# 02_FPGA_CORE.net
KiCad netlist of a schematic drawn in Altium Designer
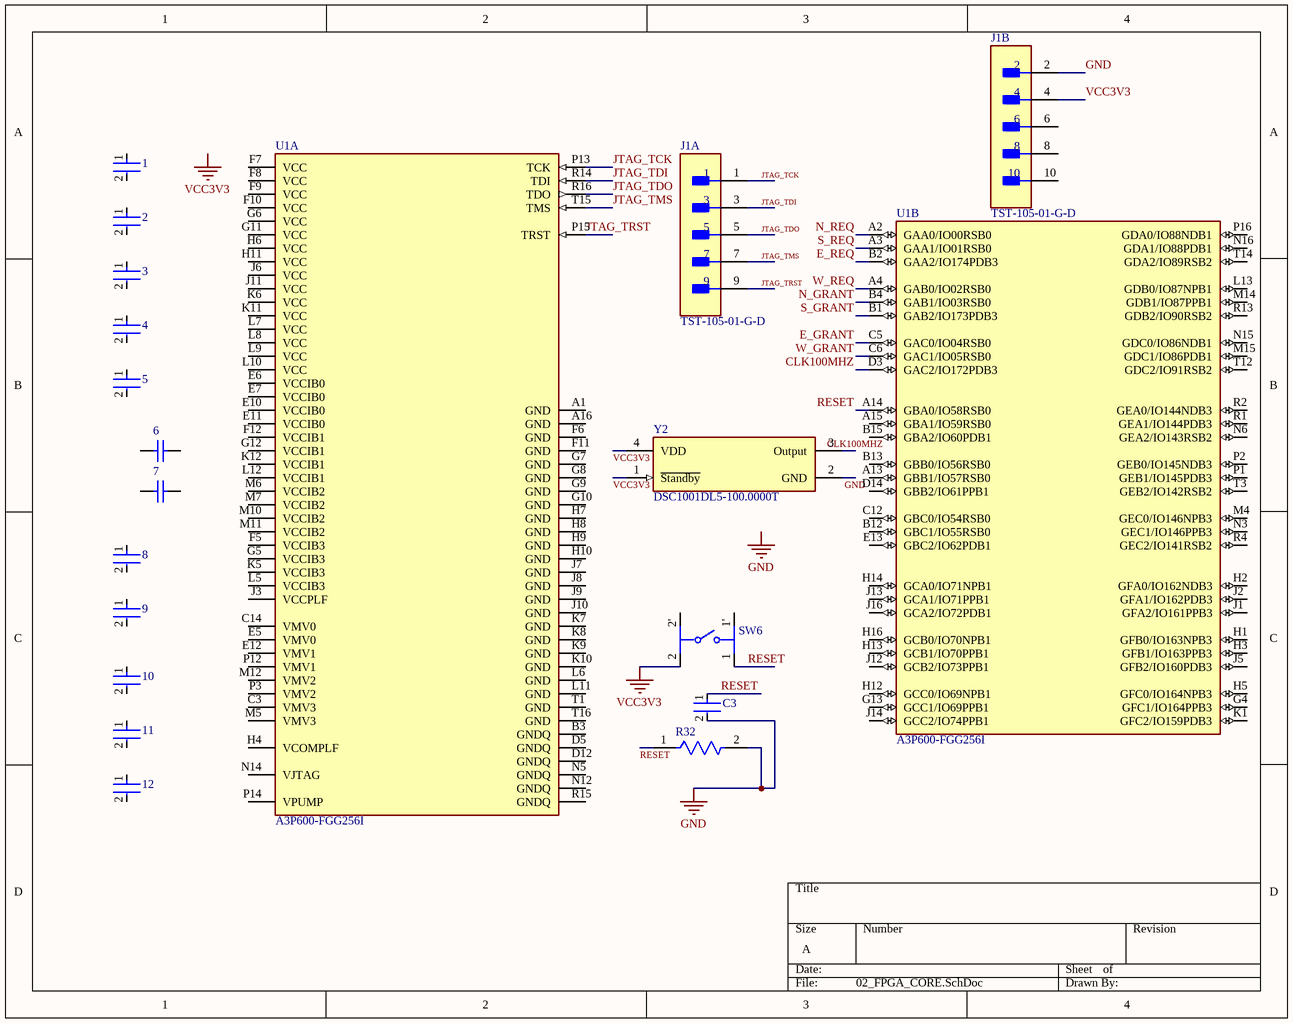
[diagram p0: 02_FPGA_CORE.SchDoc]

(export (version "E")
  (design (tool "Eeschema 10.0.6"))
  (components
    (comp (ref "1")
      (value "~")
      (footprint "FP-MC0603-IPC_B")
      (description "Ceramic Capacitor, Multilayer, Ceramic, 50V, 10% +Tol, 10% -Tol, X7R, -/+15ppm/Cel TC, 0.1uF, 0603")
      (fields (field (name "TOLERANCE") "10%"))
      (libsource (lib "Components - 29.06.26 - 21.42") (part "CMP-12266-000001-1"))
    )
    (comp (ref "2")
      (value "~")
      (footprint "FP-MC0603-IPC_B")
      (description "Ceramic Capacitor, Multilayer, Ceramic, 50V, 10% +Tol, 10% -Tol, X7R, -/+15ppm/Cel TC, 0.1uF, 0603")
      (fields (field (name "TOLERANCE") "10%"))
      (libsource (lib "Components - 29.06.26 - 21.42") (part "CMP-12266-000001-1"))
    )
    (comp (ref "3")
      (value "~")
      (footprint "FP-MC0603-IPC_B")
      (description "Ceramic Capacitor, Multilayer, Ceramic, 50V, 10% +Tol, 10% -Tol, X7R, -/+15ppm/Cel TC, 0.1uF, 0603")
      (fields (field (name "TOLERANCE") "10%"))
      (libsource (lib "Components - 29.06.26 - 21.42") (part "CMP-12266-000001-1"))
    )
    (comp (ref "4")
      (value "~")
      (footprint "FP-MC0603-IPC_B")
      (description "Ceramic Capacitor, Multilayer, Ceramic, 50V, 10% +Tol, 10% -Tol, X7R, -/+15ppm/Cel TC, 0.1uF, 0603")
      (fields (field (name "TOLERANCE") "10%"))
      (libsource (lib "Components - 29.06.26 - 21.42") (part "CMP-12266-000001-1"))
    )
    (comp (ref "5")
      (value "~")
      (footprint "FP-MC0603-IPC_B")
      (description "Ceramic Capacitor, Multilayer, Ceramic, 50V, 10% +Tol, 10% -Tol, X7R, -/+15ppm/Cel TC, 0.1uF, 0603")
      (fields (field (name "TOLERANCE") "10%"))
      (libsource (lib "Components - 29.06.26 - 21.42") (part "CMP-12266-000001-1"))
    )
    (comp (ref "6")
      (value "~")
      (footprint "CAPC2013X145X50ML20T25")
      (fields (field (name "MANUFACTURER") "Kemet") (field (name "PART NUMBER") "C0805C106K8RACTU"))
      (libsource (lib "Components - 29.06.26 - 21.58") (part "CMP-2007-01044-1"))
    )
    (comp (ref "7")
      (value "~")
      (footprint "CAPC2013X145X50ML20T25")
      (fields (field (name "MANUFACTURER") "Kemet") (field (name "PART NUMBER") "C0805C106K8RACTU"))
      (libsource (lib "Components - 29.06.26 - 21.58") (part "CMP-2007-01044-1"))
    )
    (comp (ref "8")
      (value "~")
      (footprint "FP-MC0603-IPC_B")
      (description "Ceramic Capacitor, Multilayer, Ceramic, 50V, 10% +Tol, 10% -Tol, X7R, -/+15ppm/Cel TC, 0.1uF, 0603")
      (fields (field (name "TOLERANCE") "10%"))
      (libsource (lib "Components - 29.06.26 - 21.42") (part "CMP-12266-000001-1"))
    )
    (comp (ref "9")
      (value "~")
      (footprint "FP-MC0603-IPC_B")
      (description "Ceramic Capacitor, Multilayer, Ceramic, 50V, 10% +Tol, 10% -Tol, X7R, -/+15ppm/Cel TC, 0.1uF, 0603")
      (fields (field (name "TOLERANCE") "10%"))
      (libsource (lib "Components - 29.06.26 - 21.42") (part "CMP-12266-000001-1"))
    )
    (comp (ref "10")
      (value "~")
      (footprint "FP-MC0603-IPC_B")
      (description "Ceramic Capacitor, Multilayer, Ceramic, 50V, 10% +Tol, 10% -Tol, X7R, -/+15ppm/Cel TC, 0.1uF, 0603")
      (fields (field (name "TOLERANCE") "10%"))
      (libsource (lib "Components - 29.06.26 - 21.42") (part "CMP-12266-000001-1"))
    )
    (comp (ref "11")
      (value "~")
      (footprint "FP-MC0603-IPC_B")
      (description "Ceramic Capacitor, Multilayer, Ceramic, 50V, 10% +Tol, 10% -Tol, X7R, -/+15ppm/Cel TC, 0.1uF, 0603")
      (fields (field (name "TOLERANCE") "10%"))
      (libsource (lib "Components - 29.06.26 - 21.42") (part "CMP-12266-000001-1"))
    )
    (comp (ref "12")
      (value "~")
      (footprint "FP-MC0603-IPC_B")
      (description "Ceramic Capacitor, Multilayer, Ceramic, 50V, 10% +Tol, 10% -Tol, X7R, -/+15ppm/Cel TC, 0.1uF, 0603")
      (fields (field (name "TOLERANCE") "10%"))
      (libsource (lib "Components - 29.06.26 - 21.42") (part "CMP-12266-000001-1"))
    )
    (comp (ref "C3")
      (value "~")
      (footprint "FP-MC0603-IPC_B")
      (description "Ceramic Capacitor, Multilayer, Ceramic, 50V, 10% +Tol, 10% -Tol, X7R, -/+15ppm/Cel TC, 0.1uF, 0603")
      (fields (field (name "TOLERANCE") "10%"))
      (libsource (lib "Components - 29.06.26 - 23.33") (part "CMP-12266-000001-1"))
    )
    (comp (ref "J1")
      (value "TST-105-01-G-D")
      (footprint "FP-TST-105-01-G-D-MFG")
      (description "CONN HEADER VERT 10POS 2.54MM")
      (libsource (lib "Components - 30.06.26 - 11.04") (part "CMP-02766-001680-1"))
    )
    (comp (ref "R32")
      (value "~")
      (footprint "FP-RT0603-IPC_C")
      (description "RES SMD 10K OHM 0.05% 1/10W 0603")
      (fields
        (field (name "OCTOPART") "https://octopart.com/rt0603wre0710kl-yageo-71396825")
        (field (name "MANUFACTURER") "Yageo")
      )
      (libsource (lib "Components - 29.06.26 - 23.31") (part "CMP-03412-024743-1"))
    )
    (comp (ref "SW6")
      (value "~")
      (footprint "FP-EVQ-P7A01P-MFG")
      (description "SWITCH TACTILE SPST-NO 0.05A 12V")
      (fields
        (field (name "OCTOPART") "https://octopart.com/evq-p7a01p-panasonic-29917075")
        (field (name "MANUFACTURER") "Panasonic")
      )
      (libsource (lib "Components - 29.06.26 - 23.28") (part "CMP-05618-000007-1"))
    )
    (comp (ref "U1")
      (value "A3P600-FGG256I")
      (footprint "FP-FG256-IPC_C")
      (description "A3P600-FGG256I FPGA ProASIC®3 Family 600K Gates 231MHz 130nm (CMOS) Technology 1.5V 256-Pin FBGA")
      (libsource (lib "Components - 29.06.26 - 18.48") (part "CMP-00252-99164184-1"))
    )
    (comp (ref "Y2")
      (value "DSC1001DL5-100.0000T")
      (footprint "FP-CDFN2520-4LD-PL-1-MFG")
      (libsource (lib "Components - 29.06.26 - 23.16") (part "CMP-00252-66799144-1"))
    )
  )
  (nets
    (net (code "1") (name "/CLK100MHZ") (class "Default")
      (node (ref "U1") (pin "D3") (pinfunction "GAC2/IO172PDB3_D3") (pintype "bidirectional"))
      (node (ref "Y2") (pin "3") (pinfunction "Output_3") (pintype "passive"))
    )
    (net (code "2") (name "/E_GRANT") (class "Default")
      (node (ref "U1") (pin "C5") (pinfunction "GAC0/IO04RSB0_C5") (pintype "bidirectional"))
    )
    (net (code "3") (name "/E_REQ") (class "Default")
      (node (ref "U1") (pin "B2") (pinfunction "GAA2/IO174PDB3_B2") (pintype "bidirectional"))
    )
    (net (code "4") (name "/JTAG_TCK") (class "Default")
      (node (ref "J1") (pin "1") (pinfunction "1_1") (pintype "passive"))
      (node (ref "U1") (pin "P13") (pinfunction "TCK_P13") (pintype "input"))
    )
    (net (code "5") (name "/JTAG_TDI") (class "Default")
      (node (ref "J1") (pin "3") (pinfunction "3_3") (pintype "passive"))
      (node (ref "U1") (pin "R14") (pinfunction "TDI_R14") (pintype "input"))
    )
    (net (code "6") (name "/JTAG_TDO") (class "Default")
      (node (ref "J1") (pin "5") (pinfunction "5_5") (pintype "passive"))
      (node (ref "U1") (pin "R16") (pinfunction "TDO_R16") (pintype "output"))
    )
    (net (code "7") (name "/JTAG_TMS") (class "Default")
      (node (ref "J1") (pin "7") (pinfunction "7_7") (pintype "passive"))
      (node (ref "U1") (pin "T15") (pinfunction "TMS_T15") (pintype "input"))
    )
    (net (code "8") (name "/JTAG_TRST") (class "Default")
      (node (ref "J1") (pin "9") (pinfunction "9_9") (pintype "passive"))
      (node (ref "U1") (pin "P15") (pinfunction "TRST_P15") (pintype "input"))
    )
    (net (code "9") (name "/N_GRANT") (class "Default")
      (node (ref "U1") (pin "B4") (pinfunction "GAB1/IO03RSB0_B4") (pintype "bidirectional"))
    )
    (net (code "10") (name "/N_REQ") (class "Default")
      (node (ref "U1") (pin "A2") (pinfunction "GAA0/IO00RSB0_A2") (pintype "bidirectional"))
    )
    (net (code "11") (name "/RESET") (class "Default")
      (node (ref "C3") (pin "1") (pinfunction "1_1") (pintype "passive"))
      (node (ref "R32") (pin "1") (pinfunction "1_1") (pintype "passive"))
      (node (ref "SW6") (pin "1") (pinfunction "1_1") (pintype "passive"))
      (node (ref "U1") (pin "A14") (pinfunction "GBA0/IO58RSB0_A14") (pintype "bidirectional"))
    )
    (net (code "12") (name "/S_GRANT") (class "Default")
      (node (ref "U1") (pin "B1") (pinfunction "GAB2/IO173PDB3_B1") (pintype "bidirectional"))
    )
    (net (code "13") (name "/S_REQ") (class "Default")
      (node (ref "U1") (pin "A3") (pinfunction "GAA1/IO01RSB0_A3") (pintype "bidirectional"))
    )
    (net (code "14") (name "/W_GRANT") (class "Default")
      (node (ref "U1") (pin "C6") (pinfunction "GAC1/IO05RSB0_C6") (pintype "bidirectional"))
    )
    (net (code "15") (name "/W_REQ") (class "Default")
      (node (ref "U1") (pin "A4") (pinfunction "GAB0/IO02RSB0_A4") (pintype "bidirectional"))
    )
    (net (code "16") (name "GND") (class "Default")
      (node (ref "C3") (pin "2") (pinfunction "2_2") (pintype "passive"))
      (node (ref "J1") (pin "2") (pinfunction "2_2") (pintype "passive"))
      (node (ref "R32") (pin "2") (pinfunction "2_2") (pintype "passive"))
      (node (ref "Y2") (pin "2") (pinfunction "GND_2") (pintype "power_in"))
    )
    (net (code "17") (name "VCC3V3") (class "Default")
      (node (ref "J1") (pin "4") (pinfunction "4_4") (pintype "passive"))
      (node (ref "SW6") (pin "2") (pinfunction "2_2") (pintype "passive"))
      (node (ref "Y2") (pin "1") (pinfunction "~{Standby}_1") (pintype "input"))
      (node (ref "Y2") (pin "4") (pinfunction "VDD_4") (pintype "power_in"))
    )
    (net (code "18") (name "unconnected-(1-Pad1)") (class "Default")
      (node (ref "1") (pin "1") (pinfunction "1_1") (pintype "passive"))
    )
    (net (code "19") (name "unconnected-(1-Pad2)") (class "Default")
      (node (ref "1") (pin "2") (pinfunction "2_2") (pintype "passive"))
    )
    (net (code "20") (name "unconnected-(2-Pad1)") (class "Default")
      (node (ref "2") (pin "1") (pinfunction "1_1") (pintype "passive"))
    )
    (net (code "21") (name "unconnected-(2-Pad2)") (class "Default")
      (node (ref "2") (pin "2") (pinfunction "2_2") (pintype "passive"))
    )
    (net (code "22") (name "unconnected-(3-Pad1)") (class "Default")
      (node (ref "3") (pin "1") (pinfunction "1_1") (pintype "passive"))
    )
    (net (code "23") (name "unconnected-(3-Pad2)") (class "Default")
      (node (ref "3") (pin "2") (pinfunction "2_2") (pintype "passive"))
    )
    (net (code "24") (name "unconnected-(4-Pad1)") (class "Default")
      (node (ref "4") (pin "1") (pinfunction "1_1") (pintype "passive"))
    )
    (net (code "25") (name "unconnected-(4-Pad2)") (class "Default")
      (node (ref "4") (pin "2") (pinfunction "2_2") (pintype "passive"))
    )
    (net (code "26") (name "unconnected-(5-Pad1)") (class "Default")
      (node (ref "5") (pin "1") (pinfunction "1_1") (pintype "passive"))
    )
    (net (code "27") (name "unconnected-(5-Pad2)") (class "Default")
      (node (ref "5") (pin "2") (pinfunction "2_2") (pintype "passive"))
    )
    (net (code "28") (name "unconnected-(6-Pad1)") (class "Default")
      (node (ref "6") (pin "1") (pinfunction "1_1") (pintype "passive"))
    )
    (net (code "29") (name "unconnected-(6-Pad2)") (class "Default")
      (node (ref "6") (pin "2") (pinfunction "2_2") (pintype "passive"))
    )
    (net (code "30") (name "unconnected-(7-Pad1)") (class "Default")
      (node (ref "7") (pin "1") (pinfunction "1_1") (pintype "passive"))
    )
    (net (code "31") (name "unconnected-(7-Pad2)") (class "Default")
      (node (ref "7") (pin "2") (pinfunction "2_2") (pintype "passive"))
    )
    (net (code "32") (name "unconnected-(8-Pad1)") (class "Default")
      (node (ref "8") (pin "1") (pinfunction "1_1") (pintype "passive"))
    )
    (net (code "33") (name "unconnected-(8-Pad2)") (class "Default")
      (node (ref "8") (pin "2") (pinfunction "2_2") (pintype "passive"))
    )
    (net (code "34") (name "unconnected-(9-Pad1)") (class "Default")
      (node (ref "9") (pin "1") (pinfunction "1_1") (pintype "passive"))
    )
    (net (code "35") (name "unconnected-(9-Pad2)") (class "Default")
      (node (ref "9") (pin "2") (pinfunction "2_2") (pintype "passive"))
    )
    (net (code "36") (name "unconnected-(10-Pad1)") (class "Default")
      (node (ref "10") (pin "1") (pinfunction "1_1") (pintype "passive"))
    )
    (net (code "37") (name "unconnected-(10-Pad2)") (class "Default")
      (node (ref "10") (pin "2") (pinfunction "2_2") (pintype "passive"))
    )
    (net (code "38") (name "unconnected-(11-Pad1)") (class "Default")
      (node (ref "11") (pin "1") (pinfunction "1_1") (pintype "passive"))
    )
    (net (code "39") (name "unconnected-(11-Pad2)") (class "Default")
      (node (ref "11") (pin "2") (pinfunction "2_2") (pintype "passive"))
    )
    (net (code "40") (name "unconnected-(12-Pad1)") (class "Default")
      (node (ref "12") (pin "1") (pinfunction "1_1") (pintype "passive"))
    )
    (net (code "41") (name "unconnected-(12-Pad2)") (class "Default")
      (node (ref "12") (pin "2") (pinfunction "2_2") (pintype "passive"))
    )
    (net (code "42") (name "unconnected-(J1-Pad6)") (class "Default")
      (node (ref "J1") (pin "6") (pinfunction "6_6") (pintype "passive"))
    )
    (net (code "43") (name "unconnected-(J1-Pad8)") (class "Default")
      (node (ref "J1") (pin "8") (pinfunction "8_8") (pintype "passive"))
    )
    (net (code "44") (name "unconnected-(J1-Pad10)") (class "Default")
      (node (ref "J1") (pin "10") (pinfunction "10_10") (pintype "passive"))
    )
    (net (code "45") (name "unconnected-(SW6-Pad1')") (class "Default")
      (node (ref "SW6") (pin "1'") (pinfunction "1'_1'") (pintype "passive"))
    )
    (net (code "46") (name "unconnected-(SW6-Pad2')") (class "Default")
      (node (ref "SW6") (pin "2'") (pinfunction "2'_2'") (pintype "passive"))
    )
    (net (code "47") (name "unconnected-(U1A-GND-PadA1)") (class "Default")
      (node (ref "U1") (pin "A1") (pinfunction "GND_A1") (pintype "power_in"))
    )
    (net (code "48") (name "unconnected-(U1A-GND-PadA16)") (class "Default")
      (node (ref "U1") (pin "A16") (pinfunction "GND_A16") (pintype "power_in"))
    )
    (net (code "49") (name "unconnected-(U1A-GND-PadF6)") (class "Default")
      (node (ref "U1") (pin "F6") (pinfunction "GND_F6") (pintype "power_in"))
    )
    (net (code "50") (name "unconnected-(U1A-GND-PadF11)") (class "Default")
      (node (ref "U1") (pin "F11") (pinfunction "GND_F11") (pintype "power_in"))
    )
    (net (code "51") (name "unconnected-(U1A-GND-PadG7)") (class "Default")
      (node (ref "U1") (pin "G7") (pinfunction "GND_G7") (pintype "power_in"))
    )
    (net (code "52") (name "unconnected-(U1A-GND-PadG8)") (class "Default")
      (node (ref "U1") (pin "G8") (pinfunction "GND_G8") (pintype "power_in"))
    )
    (net (code "53") (name "unconnected-(U1A-GND-PadG9)") (class "Default")
      (node (ref "U1") (pin "G9") (pinfunction "GND_G9") (pintype "power_in"))
    )
    (net (code "54") (name "unconnected-(U1A-GND-PadG10)") (class "Default")
      (node (ref "U1") (pin "G10") (pinfunction "GND_G10") (pintype "power_in"))
    )
    (net (code "55") (name "unconnected-(U1A-GND-PadH7)") (class "Default")
      (node (ref "U1") (pin "H7") (pinfunction "GND_H7") (pintype "power_in"))
    )
    (net (code "56") (name "unconnected-(U1A-GND-PadH8)") (class "Default")
      (node (ref "U1") (pin "H8") (pinfunction "GND_H8") (pintype "power_in"))
    )
    (net (code "57") (name "unconnected-(U1A-GND-PadH9)") (class "Default")
      (node (ref "U1") (pin "H9") (pinfunction "GND_H9") (pintype "power_in"))
    )
    (net (code "58") (name "unconnected-(U1A-GND-PadH10)") (class "Default")
      (node (ref "U1") (pin "H10") (pinfunction "GND_H10") (pintype "power_in"))
    )
    (net (code "59") (name "unconnected-(U1A-GND-PadJ7)") (class "Default")
      (node (ref "U1") (pin "J7") (pinfunction "GND_J7") (pintype "power_in"))
    )
    (net (code "60") (name "unconnected-(U1A-GND-PadJ8)") (class "Default")
      (node (ref "U1") (pin "J8") (pinfunction "GND_J8") (pintype "power_in"))
    )
    (net (code "61") (name "unconnected-(U1A-GND-PadJ9)") (class "Default")
      (node (ref "U1") (pin "J9") (pinfunction "GND_J9") (pintype "power_in"))
    )
    (net (code "62") (name "unconnected-(U1A-GND-PadJ10)") (class "Default")
      (node (ref "U1") (pin "J10") (pinfunction "GND_J10") (pintype "power_in"))
    )
    (net (code "63") (name "unconnected-(U1A-GND-PadK7)") (class "Default")
      (node (ref "U1") (pin "K7") (pinfunction "GND_K7") (pintype "power_in"))
    )
    (net (code "64") (name "unconnected-(U1A-GND-PadK8)") (class "Default")
      (node (ref "U1") (pin "K8") (pinfunction "GND_K8") (pintype "power_in"))
    )
    (net (code "65") (name "unconnected-(U1A-GND-PadK9)") (class "Default")
      (node (ref "U1") (pin "K9") (pinfunction "GND_K9") (pintype "power_in"))
    )
    (net (code "66") (name "unconnected-(U1A-GND-PadK10)") (class "Default")
      (node (ref "U1") (pin "K10") (pinfunction "GND_K10") (pintype "power_in"))
    )
    (net (code "67") (name "unconnected-(U1A-GND-PadL6)") (class "Default")
      (node (ref "U1") (pin "L6") (pinfunction "GND_L6") (pintype "power_in"))
    )
    (net (code "68") (name "unconnected-(U1A-GND-PadL11)") (class "Default")
      (node (ref "U1") (pin "L11") (pinfunction "GND_L11") (pintype "power_in"))
    )
    (net (code "69") (name "unconnected-(U1A-GND-PadT1)") (class "Default")
      (node (ref "U1") (pin "T1") (pinfunction "GND_T1") (pintype "power_in"))
    )
    (net (code "70") (name "unconnected-(U1A-GND-PadT16)") (class "Default")
      (node (ref "U1") (pin "T16") (pinfunction "GND_T16") (pintype "power_in"))
    )
    (net (code "71") (name "unconnected-(U1A-GNDQ-PadB3)") (class "Default")
      (node (ref "U1") (pin "B3") (pinfunction "GNDQ_B3") (pintype "power_in"))
    )
    (net (code "72") (name "unconnected-(U1A-GNDQ-PadD5)") (class "Default")
      (node (ref "U1") (pin "D5") (pinfunction "GNDQ_D5") (pintype "power_in"))
    )
    (net (code "73") (name "unconnected-(U1A-GNDQ-PadD12)") (class "Default")
      (node (ref "U1") (pin "D12") (pinfunction "GNDQ_D12") (pintype "power_in"))
    )
    (net (code "74") (name "unconnected-(U1A-GNDQ-PadN5)") (class "Default")
      (node (ref "U1") (pin "N5") (pinfunction "GNDQ_N5") (pintype "power_in"))
    )
    (net (code "75") (name "unconnected-(U1A-GNDQ-PadN12)") (class "Default")
      (node (ref "U1") (pin "N12") (pinfunction "GNDQ_N12") (pintype "power_in"))
    )
    (net (code "76") (name "unconnected-(U1A-GNDQ-PadR15)") (class "Default")
      (node (ref "U1") (pin "R15") (pinfunction "GNDQ_R15") (pintype "power_in"))
    )
    (net (code "77") (name "unconnected-(U1A-VCC-PadF7)") (class "Default")
      (node (ref "U1") (pin "F7") (pinfunction "VCC_F7") (pintype "power_in"))
    )
    (net (code "78") (name "unconnected-(U1A-VCC-PadF8)") (class "Default")
      (node (ref "U1") (pin "F8") (pinfunction "VCC_F8") (pintype "power_in"))
    )
    (net (code "79") (name "unconnected-(U1A-VCC-PadF9)") (class "Default")
      (node (ref "U1") (pin "F9") (pinfunction "VCC_F9") (pintype "power_in"))
    )
    (net (code "80") (name "unconnected-(U1A-VCC-PadF10)") (class "Default")
      (node (ref "U1") (pin "F10") (pinfunction "VCC_F10") (pintype "power_in"))
    )
    (net (code "81") (name "unconnected-(U1A-VCC-PadG6)") (class "Default")
      (node (ref "U1") (pin "G6") (pinfunction "VCC_G6") (pintype "power_in"))
    )
    (net (code "82") (name "unconnected-(U1A-VCC-PadG11)") (class "Default")
      (node (ref "U1") (pin "G11") (pinfunction "VCC_G11") (pintype "power_in"))
    )
    (net (code "83") (name "unconnected-(U1A-VCC-PadH6)") (class "Default")
      (node (ref "U1") (pin "H6") (pinfunction "VCC_H6") (pintype "power_in"))
    )
    (net (code "84") (name "unconnected-(U1A-VCC-PadH11)") (class "Default")
      (node (ref "U1") (pin "H11") (pinfunction "VCC_H11") (pintype "power_in"))
    )
    (net (code "85") (name "unconnected-(U1A-VCC-PadJ6)") (class "Default")
      (node (ref "U1") (pin "J6") (pinfunction "VCC_J6") (pintype "power_in"))
    )
    (net (code "86") (name "unconnected-(U1A-VCC-PadJ11)") (class "Default")
      (node (ref "U1") (pin "J11") (pinfunction "VCC_J11") (pintype "power_in"))
    )
    (net (code "87") (name "unconnected-(U1A-VCC-PadK6)") (class "Default")
      (node (ref "U1") (pin "K6") (pinfunction "VCC_K6") (pintype "power_in"))
    )
    (net (code "88") (name "unconnected-(U1A-VCC-PadK11)") (class "Default")
      (node (ref "U1") (pin "K11") (pinfunction "VCC_K11") (pintype "power_in"))
    )
    (net (code "89") (name "unconnected-(U1A-VCC-PadL7)") (class "Default")
      (node (ref "U1") (pin "L7") (pinfunction "VCC_L7") (pintype "power_in"))
    )
    (net (code "90") (name "unconnected-(U1A-VCC-PadL8)") (class "Default")
      (node (ref "U1") (pin "L8") (pinfunction "VCC_L8") (pintype "power_in"))
    )
    (net (code "91") (name "unconnected-(U1A-VCC-PadL9)") (class "Default")
      (node (ref "U1") (pin "L9") (pinfunction "VCC_L9") (pintype "power_in"))
    )
    (net (code "92") (name "unconnected-(U1A-VCC-PadL10)") (class "Default")
      (node (ref "U1") (pin "L10") (pinfunction "VCC_L10") (pintype "power_in"))
    )
    (net (code "93") (name "unconnected-(U1A-VCCIB0-PadE6)") (class "Default")
      (node (ref "U1") (pin "E6") (pinfunction "VCCIB0_E6") (pintype "power_in"))
    )
    (net (code "94") (name "unconnected-(U1A-VCCIB0-PadE7)") (class "Default")
      (node (ref "U1") (pin "E7") (pinfunction "VCCIB0_E7") (pintype "power_in"))
    )
    (net (code "95") (name "unconnected-(U1A-VCCIB0-PadE10)") (class "Default")
      (node (ref "U1") (pin "E10") (pinfunction "VCCIB0_E10") (pintype "power_in"))
    )
    (net (code "96") (name "unconnected-(U1A-VCCIB0-PadE11)") (class "Default")
      (node (ref "U1") (pin "E11") (pinfunction "VCCIB0_E11") (pintype "power_in"))
    )
    (net (code "97") (name "unconnected-(U1A-VCCIB1-PadF12)") (class "Default")
      (node (ref "U1") (pin "F12") (pinfunction "VCCIB1_F12") (pintype "power_in"))
    )
    (net (code "98") (name "unconnected-(U1A-VCCIB1-PadG12)") (class "Default")
      (node (ref "U1") (pin "G12") (pinfunction "VCCIB1_G12") (pintype "power_in"))
    )
    (net (code "99") (name "unconnected-(U1A-VCCIB1-PadK12)") (class "Default")
      (node (ref "U1") (pin "K12") (pinfunction "VCCIB1_K12") (pintype "power_in"))
    )
    (net (code "100") (name "unconnected-(U1A-VCCIB1-PadL12)") (class "Default")
      (node (ref "U1") (pin "L12") (pinfunction "VCCIB1_L12") (pintype "power_in"))
    )
    (net (code "101") (name "unconnected-(U1A-VCCIB2-PadM6)") (class "Default")
      (node (ref "U1") (pin "M6") (pinfunction "VCCIB2_M6") (pintype "power_in"))
    )
    (net (code "102") (name "unconnected-(U1A-VCCIB2-PadM7)") (class "Default")
      (node (ref "U1") (pin "M7") (pinfunction "VCCIB2_M7") (pintype "power_in"))
    )
    (net (code "103") (name "unconnected-(U1A-VCCIB2-PadM10)") (class "Default")
      (node (ref "U1") (pin "M10") (pinfunction "VCCIB2_M10") (pintype "power_in"))
    )
    (net (code "104") (name "unconnected-(U1A-VCCIB2-PadM11)") (class "Default")
      (node (ref "U1") (pin "M11") (pinfunction "VCCIB2_M11") (pintype "power_in"))
    )
    (net (code "105") (name "unconnected-(U1A-VCCIB3-PadF5)") (class "Default")
      (node (ref "U1") (pin "F5") (pinfunction "VCCIB3_F5") (pintype "power_in"))
    )
    (net (code "106") (name "unconnected-(U1A-VCCIB3-PadG5)") (class "Default")
      (node (ref "U1") (pin "G5") (pinfunction "VCCIB3_G5") (pintype "power_in"))
    )
    (net (code "107") (name "unconnected-(U1A-VCCIB3-PadK5)") (class "Default")
      (node (ref "U1") (pin "K5") (pinfunction "VCCIB3_K5") (pintype "power_in"))
    )
    (net (code "108") (name "unconnected-(U1A-VCCIB3-PadL5)") (class "Default")
      (node (ref "U1") (pin "L5") (pinfunction "VCCIB3_L5") (pintype "power_in"))
    )
    (net (code "109") (name "unconnected-(U1A-VCCPLF-PadJ3)") (class "Default")
      (node (ref "U1") (pin "J3") (pinfunction "VCCPLF_J3") (pintype "power_in"))
    )
    (net (code "110") (name "unconnected-(U1A-VCOMPLF-PadH4)") (class "Default")
      (node (ref "U1") (pin "H4") (pinfunction "VCOMPLF_H4") (pintype "power_in"))
    )
    (net (code "111") (name "unconnected-(U1A-VJTAG-PadN14)") (class "Default")
      (node (ref "U1") (pin "N14") (pinfunction "VJTAG_N14") (pintype "power_in"))
    )
    (net (code "112") (name "unconnected-(U1A-VMV0-PadC14)") (class "Default")
      (node (ref "U1") (pin "C14") (pinfunction "VMV0_C14") (pintype "power_in"))
    )
    (net (code "113") (name "unconnected-(U1A-VMV0-PadE5)") (class "Default")
      (node (ref "U1") (pin "E5") (pinfunction "VMV0_E5") (pintype "power_in"))
    )
    (net (code "114") (name "unconnected-(U1A-VMV1-PadE12)") (class "Default")
      (node (ref "U1") (pin "E12") (pinfunction "VMV1_E12") (pintype "power_in"))
    )
    (net (code "115") (name "unconnected-(U1A-VMV1-PadP12)") (class "Default")
      (node (ref "U1") (pin "P12") (pinfunction "VMV1_P12") (pintype "power_in"))
    )
    (net (code "116") (name "unconnected-(U1A-VMV2-PadM12)") (class "Default")
      (node (ref "U1") (pin "M12") (pinfunction "VMV2_M12") (pintype "power_in"))
    )
    (net (code "117") (name "unconnected-(U1A-VMV2-PadP3)") (class "Default")
      (node (ref "U1") (pin "P3") (pinfunction "VMV2_P3") (pintype "power_in"))
    )
    (net (code "118") (name "unconnected-(U1A-VMV3-PadC3)") (class "Default")
      (node (ref "U1") (pin "C3") (pinfunction "VMV3_C3") (pintype "power_in"))
    )
    (net (code "119") (name "unconnected-(U1A-VMV3-PadM5)") (class "Default")
      (node (ref "U1") (pin "M5") (pinfunction "VMV3_M5") (pintype "power_in"))
    )
    (net (code "120") (name "unconnected-(U1A-VPUMP-PadP14)") (class "Default")
      (node (ref "U1") (pin "P14") (pinfunction "VPUMP_P14") (pintype "power_in"))
    )
    (net (code "121") (name "unconnected-(U1B-GBA1{slash}IO59RSB0-PadA15)") (class "Default")
      (node (ref "U1") (pin "A15") (pinfunction "GBA1/IO59RSB0_A15") (pintype "bidirectional"))
    )
    (net (code "122") (name "unconnected-(U1B-GBA2{slash}IO60PDB1-PadB15)") (class "Default")
      (node (ref "U1") (pin "B15") (pinfunction "GBA2/IO60PDB1_B15") (pintype "bidirectional"))
    )
    (net (code "123") (name "unconnected-(U1B-GBB0{slash}IO56RSB0-PadB13)") (class "Default")
      (node (ref "U1") (pin "B13") (pinfunction "GBB0/IO56RSB0_B13") (pintype "bidirectional"))
    )
    (net (code "124") (name "unconnected-(U1B-GBB1{slash}IO57RSB0-PadA13)") (class "Default")
      (node (ref "U1") (pin "A13") (pinfunction "GBB1/IO57RSB0_A13") (pintype "bidirectional"))
    )
    (net (code "125") (name "unconnected-(U1B-GBB2{slash}IO61PPB1-PadD14)") (class "Default")
      (node (ref "U1") (pin "D14") (pinfunction "GBB2/IO61PPB1_D14") (pintype "bidirectional"))
    )
    (net (code "126") (name "unconnected-(U1B-GBC0{slash}IO54RSB0-PadC12)") (class "Default")
      (node (ref "U1") (pin "C12") (pinfunction "GBC0/IO54RSB0_C12") (pintype "bidirectional"))
    )
    (net (code "127") (name "unconnected-(U1B-GBC1{slash}IO55RSB0-PadB12)") (class "Default")
      (node (ref "U1") (pin "B12") (pinfunction "GBC1/IO55RSB0_B12") (pintype "bidirectional"))
    )
    (net (code "128") (name "unconnected-(U1B-GBC2{slash}IO62PDB1-PadE13)") (class "Default")
      (node (ref "U1") (pin "E13") (pinfunction "GBC2/IO62PDB1_E13") (pintype "bidirectional"))
    )
    (net (code "129") (name "unconnected-(U1B-GCA0{slash}IO71NPB1-PadH14)") (class "Default")
      (node (ref "U1") (pin "H14") (pinfunction "GCA0/IO71NPB1_H14") (pintype "bidirectional"))
    )
    (net (code "130") (name "unconnected-(U1B-GCA1{slash}IO71PPB1-PadJ13)") (class "Default")
      (node (ref "U1") (pin "J13") (pinfunction "GCA1/IO71PPB1_J13") (pintype "bidirectional"))
    )
    (net (code "131") (name "unconnected-(U1B-GCA2{slash}IO72PDB1-PadJ16)") (class "Default")
      (node (ref "U1") (pin "J16") (pinfunction "GCA2/IO72PDB1_J16") (pintype "bidirectional"))
    )
    (net (code "132") (name "unconnected-(U1B-GCB0{slash}IO70NPB1-PadH16)") (class "Default")
      (node (ref "U1") (pin "H16") (pinfunction "GCB0/IO70NPB1_H16") (pintype "bidirectional"))
    )
    (net (code "133") (name "unconnected-(U1B-GCB1{slash}IO70PPB1-PadH13)") (class "Default")
      (node (ref "U1") (pin "H13") (pinfunction "GCB1/IO70PPB1_H13") (pintype "bidirectional"))
    )
    (net (code "134") (name "unconnected-(U1B-GCB2{slash}IO73PPB1-PadJ12)") (class "Default")
      (node (ref "U1") (pin "J12") (pinfunction "GCB2/IO73PPB1_J12") (pintype "bidirectional"))
    )
    (net (code "135") (name "unconnected-(U1B-GCC0{slash}IO69NPB1-PadH12)") (class "Default")
      (node (ref "U1") (pin "H12") (pinfunction "GCC0/IO69NPB1_H12") (pintype "bidirectional"))
    )
    (net (code "136") (name "unconnected-(U1B-GCC1{slash}IO69PPB1-PadG13)") (class "Default")
      (node (ref "U1") (pin "G13") (pinfunction "GCC1/IO69PPB1_G13") (pintype "bidirectional"))
    )
    (net (code "137") (name "unconnected-(U1B-GCC2{slash}IO74PPB1-PadJ14)") (class "Default")
      (node (ref "U1") (pin "J14") (pinfunction "GCC2/IO74PPB1_J14") (pintype "bidirectional"))
    )
    (net (code "138") (name "unconnected-(U1B-GDA0{slash}IO88NDB1-PadP16)") (class "Default")
      (node (ref "U1") (pin "P16") (pinfunction "GDA0/IO88NDB1_P16") (pintype "bidirectional"))
    )
    (net (code "139") (name "unconnected-(U1B-GDA1{slash}IO88PDB1-PadN16)") (class "Default")
      (node (ref "U1") (pin "N16") (pinfunction "GDA1/IO88PDB1_N16") (pintype "bidirectional"))
    )
    (net (code "140") (name "unconnected-(U1B-GDA2{slash}IO89RSB2-PadT14)") (class "Default")
      (node (ref "U1") (pin "T14") (pinfunction "GDA2/IO89RSB2_T14") (pintype "bidirectional"))
    )
    (net (code "141") (name "unconnected-(U1B-GDB0{slash}IO87NPB1-PadL13)") (class "Default")
      (node (ref "U1") (pin "L13") (pinfunction "GDB0/IO87NPB1_L13") (pintype "bidirectional"))
    )
    (net (code "142") (name "unconnected-(U1B-GDB1{slash}IO87PPB1-PadM14)") (class "Default")
      (node (ref "U1") (pin "M14") (pinfunction "GDB1/IO87PPB1_M14") (pintype "bidirectional"))
    )
    (net (code "143") (name "unconnected-(U1B-GDB2{slash}IO90RSB2-PadR13)") (class "Default")
      (node (ref "U1") (pin "R13") (pinfunction "GDB2/IO90RSB2_R13") (pintype "bidirectional"))
    )
    (net (code "144") (name "unconnected-(U1B-GDC0{slash}IO86NDB1-PadN15)") (class "Default")
      (node (ref "U1") (pin "N15") (pinfunction "GDC0/IO86NDB1_N15") (pintype "bidirectional"))
    )
    (net (code "145") (name "unconnected-(U1B-GDC1{slash}IO86PDB1-PadM15)") (class "Default")
      (node (ref "U1") (pin "M15") (pinfunction "GDC1/IO86PDB1_M15") (pintype "bidirectional"))
    )
    (net (code "146") (name "unconnected-(U1B-GDC2{slash}IO91RSB2-PadT12)") (class "Default")
      (node (ref "U1") (pin "T12") (pinfunction "GDC2/IO91RSB2_T12") (pintype "bidirectional"))
    )
    (net (code "147") (name "unconnected-(U1B-GEA0{slash}IO144NDB3-PadR2)") (class "Default")
      (node (ref "U1") (pin "R2") (pinfunction "GEA0/IO144NDB3_R2") (pintype "bidirectional"))
    )
    (net (code "148") (name "unconnected-(U1B-GEA1{slash}IO144PDB3-PadR1)") (class "Default")
      (node (ref "U1") (pin "R1") (pinfunction "GEA1/IO144PDB3_R1") (pintype "bidirectional"))
    )
    (net (code "149") (name "unconnected-(U1B-GEA2{slash}IO143RSB2-PadN6)") (class "Default")
      (node (ref "U1") (pin "N6") (pinfunction "GEA2/IO143RSB2_N6") (pintype "bidirectional"))
    )
    (net (code "150") (name "unconnected-(U1B-GEB0{slash}IO145NDB3-PadP2)") (class "Default")
      (node (ref "U1") (pin "P2") (pinfunction "GEB0/IO145NDB3_P2") (pintype "bidirectional"))
    )
    (net (code "151") (name "unconnected-(U1B-GEB1{slash}IO145PDB3-PadP1)") (class "Default")
      (node (ref "U1") (pin "P1") (pinfunction "GEB1/IO145PDB3_P1") (pintype "bidirectional"))
    )
    (net (code "152") (name "unconnected-(U1B-GEB2{slash}IO142RSB2-PadT3)") (class "Default")
      (node (ref "U1") (pin "T3") (pinfunction "GEB2/IO142RSB2_T3") (pintype "bidirectional"))
    )
    (net (code "153") (name "unconnected-(U1B-GEC0{slash}IO146NPB3-PadM4)") (class "Default")
      (node (ref "U1") (pin "M4") (pinfunction "GEC0/IO146NPB3_M4") (pintype "bidirectional"))
    )
    (net (code "154") (name "unconnected-(U1B-GEC1{slash}IO146PPB3-PadN3)") (class "Default")
      (node (ref "U1") (pin "N3") (pinfunction "GEC1/IO146PPB3_N3") (pintype "bidirectional"))
    )
    (net (code "155") (name "unconnected-(U1B-GEC2{slash}IO141RSB2-PadR4)") (class "Default")
      (node (ref "U1") (pin "R4") (pinfunction "GEC2/IO141RSB2_R4") (pintype "bidirectional"))
    )
    (net (code "156") (name "unconnected-(U1B-GFA0{slash}IO162NDB3-PadH2)") (class "Default")
      (node (ref "U1") (pin "H2") (pinfunction "GFA0/IO162NDB3_H2") (pintype "bidirectional"))
    )
    (net (code "157") (name "unconnected-(U1B-GFA1{slash}IO162PDB3-PadJ2)") (class "Default")
      (node (ref "U1") (pin "J2") (pinfunction "GFA1/IO162PDB3_J2") (pintype "bidirectional"))
    )
    (net (code "158") (name "unconnected-(U1B-GFA2{slash}IO161PPB3-PadJ1)") (class "Default")
      (node (ref "U1") (pin "J1") (pinfunction "GFA2/IO161PPB3_J1") (pintype "bidirectional"))
    )
    (net (code "159") (name "unconnected-(U1B-GFB0{slash}IO163NPB3-PadH1)") (class "Default")
      (node (ref "U1") (pin "H1") (pinfunction "GFB0/IO163NPB3_H1") (pintype "bidirectional"))
    )
    (net (code "160") (name "unconnected-(U1B-GFB1{slash}IO163PPB3-PadH3)") (class "Default")
      (node (ref "U1") (pin "H3") (pinfunction "GFB1/IO163PPB3_H3") (pintype "bidirectional"))
    )
    (net (code "161") (name "unconnected-(U1B-GFB2{slash}IO160PDB3-PadJ5)") (class "Default")
      (node (ref "U1") (pin "J5") (pinfunction "GFB2/IO160PDB3_J5") (pintype "bidirectional"))
    )
    (net (code "162") (name "unconnected-(U1B-GFC0{slash}IO164NPB3-PadH5)") (class "Default")
      (node (ref "U1") (pin "H5") (pinfunction "GFC0/IO164NPB3_H5") (pintype "bidirectional"))
    )
    (net (code "163") (name "unconnected-(U1B-GFC1{slash}IO164PPB3-PadG4)") (class "Default")
      (node (ref "U1") (pin "G4") (pinfunction "GFC1/IO164PPB3_G4") (pintype "bidirectional"))
    )
    (net (code "164") (name "unconnected-(U1B-GFC2{slash}IO159PDB3-PadK1)") (class "Default")
      (node (ref "U1") (pin "K1") (pinfunction "GFC2/IO159PDB3_K1") (pintype "bidirectional"))
    )
  )
)
